# My_STM32_BOARD_SCH.net
KiCad netlist of a schematic drawn in Altium Designer
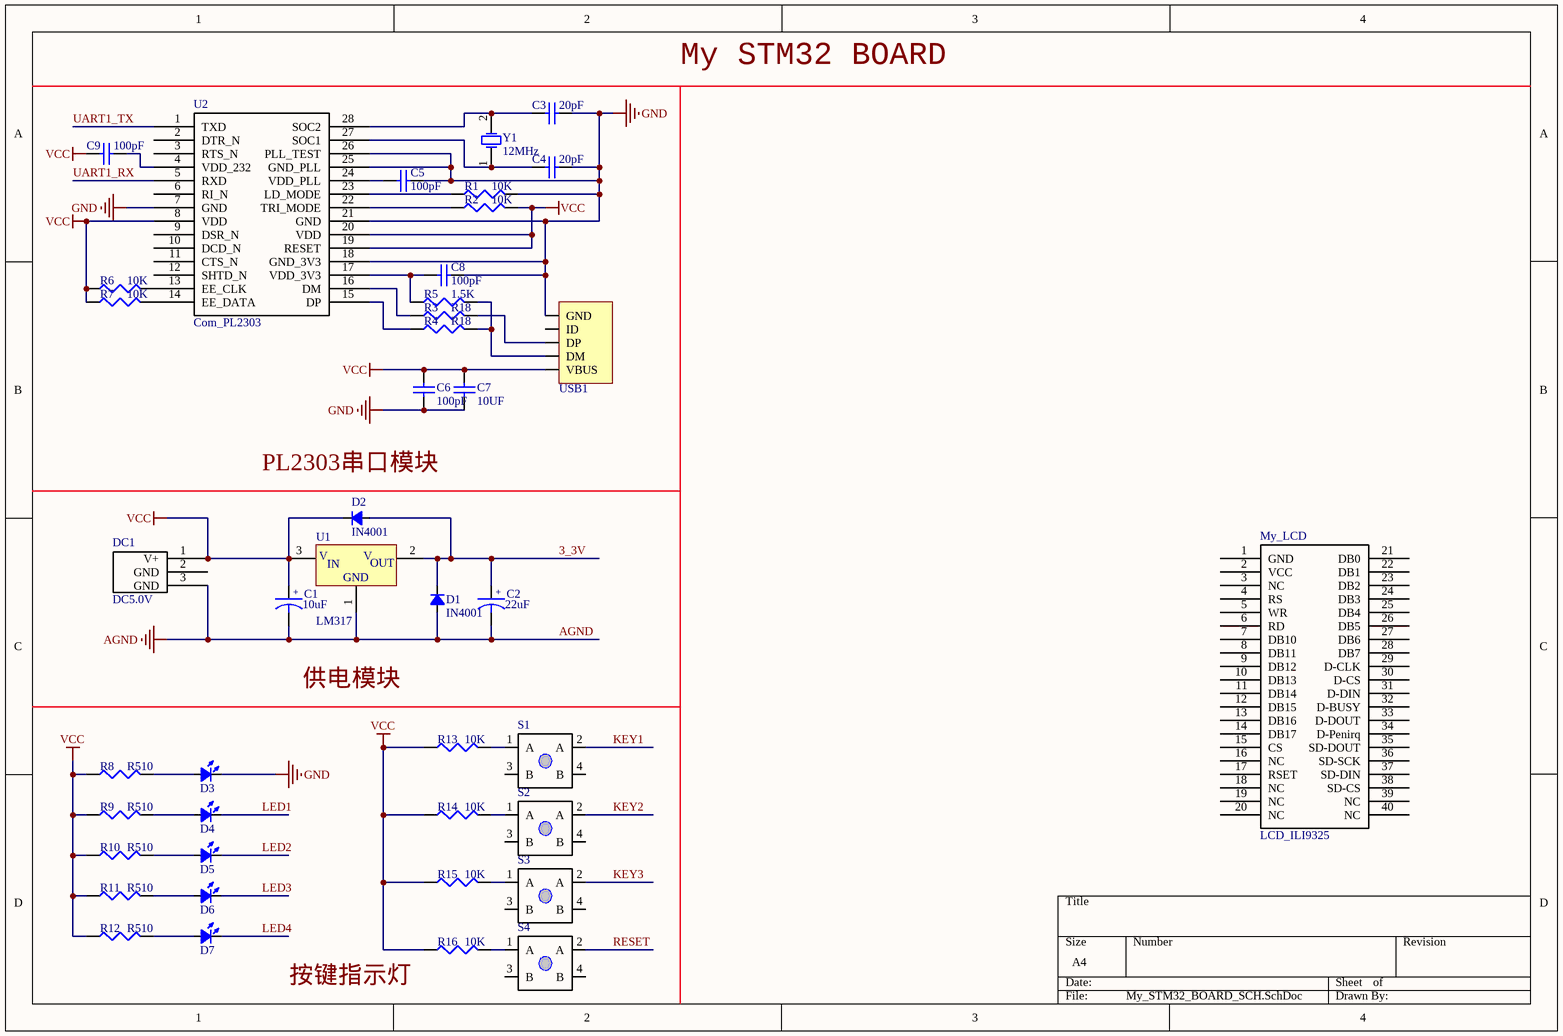
[diagram p0: My_STM32_BOARD_SCH.SchDoc]

(export (version "E")
  (design (tool "Eeschema 10.0.6"))
  (components
    (comp (ref "C1")
      (value "Cap_Pol")
      (footprint "Cap_Pol_F5")
      (description "Capacitor")
      (fields (field (name "ALTIUM_UNNAMED_1") "10uF"))
      (libsource (lib "My_Integrated_Library") (part "Cap_Pol"))
    )
    (comp (ref "C2")
      (value "22uF")
      (footprint "Cap_Pol_F6")
      (description "Capacitor")
      (fields (field (name "Comment") "Cap_Pol"))
      (libsource (lib "My_Integrated_Library") (part "Cap_Pol"))
    )
    (comp (ref "C3")
      (value "20pF")
      (footprint "0402")
      (description "Capacitor")
      (fields (field (name "Comment") "Cap") (field (name "PUBLISHER") "Altium Limited"))
      (libsource (lib "Miscellaneous Devices") (part "Cap"))
    )
    (comp (ref "C4")
      (value "20pF")
      (footprint "0402")
      (description "Capacitor")
      (fields (field (name "Comment") "Cap") (field (name "PUBLISHER") "Altium Limited"))
      (libsource (lib "Miscellaneous Devices") (part "Cap"))
    )
    (comp (ref "C5")
      (value "100pF")
      (footprint "0402")
      (description "Capacitor")
      (fields (field (name "Comment") "Cap") (field (name "PUBLISHER") "Altium Limited"))
      (libsource (lib "Miscellaneous Devices") (part "Cap"))
    )
    (comp (ref "C6")
      (value "100pF")
      (footprint "0402")
      (description "Capacitor")
      (fields (field (name "Comment") "Cap") (field (name "PUBLISHER") "Altium Limited"))
      (libsource (lib "Miscellaneous Devices") (part "Cap"))
    )
    (comp (ref "C7")
      (value "10UF")
      (footprint "2029")
      (description "Capacitor")
      (fields (field (name "Comment") "Cap") (field (name "PUBLISHER") "Altium Limited"))
      (libsource (lib "Miscellaneous Devices") (part "Cap"))
    )
    (comp (ref "C8")
      (value "100pF")
      (footprint "0402")
      (description "Capacitor")
      (fields (field (name "Comment") "Cap") (field (name "PUBLISHER") "Altium Limited"))
      (libsource (lib "Miscellaneous Devices") (part "Cap"))
    )
    (comp (ref "C9")
      (value "100pF")
      (footprint "0402")
      (description "Capacitor")
      (fields (field (name "Comment") "Cap") (field (name "PUBLISHER") "Altium Limited"))
      (libsource (lib "Miscellaneous Devices") (part "Cap"))
    )
    (comp (ref "D1")
      (value "IN4001")
      (footprint "DIODE_DO-214AC")
      (description "Diode")
      (libsource (lib "My_Integrated_Library") (part "Diode_SMA"))
    )
    (comp (ref "D2")
      (value "IN4001")
      (footprint "DIODE_DO-214AC")
      (description "Diode")
      (libsource (lib "My_Integrated_Library") (part "Diode_SMA"))
    )
    (comp (ref "D3")
      (value "LED_0805")
      (footprint "LED_0805_RED")
      (description "LED")
      (libsource (lib "My_Integrated_Library") (part "LED_0805"))
    )
    (comp (ref "D4")
      (value "LED_0805")
      (footprint "LED_1206_BLUE")
      (description "LED")
      (libsource (lib "My_Integrated_Library") (part "LED_0805"))
    )
    (comp (ref "D5")
      (value "LED_0805")
      (footprint "LED_1206_BLUE")
      (description "LED")
      (libsource (lib "My_Integrated_Library") (part "LED_0805"))
    )
    (comp (ref "D6")
      (value "LED_0805")
      (footprint "LED_1206_BLUE")
      (description "LED")
      (libsource (lib "My_Integrated_Library") (part "LED_0805"))
    )
    (comp (ref "D7")
      (value "LED_0805")
      (footprint "LED_1206_BLUE")
      (description "LED")
      (libsource (lib "My_Integrated_Library") (part "LED_0805"))
    )
    (comp (ref "DC1")
      (value "DC5.0V")
      (footprint "DC_5V")
      (libsource (lib "My_Integrated_Library") (part "DC5V"))
    )
    (comp (ref "My_LCD")
      (value "LCD_ILI9325")
      (footprint "ILI9325")
      (description "LCD ILI9325")
      (libsource (lib "My_Integrated_Library") (part "LCD_ILI9325"))
    )
    (comp (ref "R1")
      (value "10K")
      (footprint "6-0805_N")
      (description "Resistor")
      (fields (field (name "Comment") "Res3") (field (name "PUBLISHER") "Altium Limited"))
      (libsource (lib "Miscellaneous Devices") (part "Res3"))
    )
    (comp (ref "R2")
      (value "10K")
      (footprint "6-0805_N")
      (description "Resistor")
      (fields (field (name "Comment") "Res3") (field (name "PUBLISHER") "Altium Limited"))
      (libsource (lib "Miscellaneous Devices") (part "Res3"))
    )
    (comp (ref "R3")
      (value "R18")
      (footprint "6-0805_N")
      (description "Resistor")
      (fields (field (name "Comment") "Res3") (field (name "PUBLISHER") "Altium Limited"))
      (libsource (lib "Miscellaneous Devices") (part "Res3"))
    )
    (comp (ref "R4")
      (value "R18")
      (footprint "6-0805_N")
      (description "Resistor")
      (fields (field (name "Comment") "Res3") (field (name "PUBLISHER") "Altium Limited"))
      (libsource (lib "Miscellaneous Devices") (part "Res3"))
    )
    (comp (ref "R5")
      (value "1.5K")
      (footprint "6-0805_N")
      (description "Resistor")
      (fields (field (name "Comment") "Res3") (field (name "PUBLISHER") "Altium Limited"))
      (libsource (lib "Miscellaneous Devices") (part "Res3"))
    )
    (comp (ref "R6")
      (value "10K")
      (footprint "6-0805_N")
      (description "Resistor")
      (fields (field (name "Comment") "Res3") (field (name "PUBLISHER") "Altium Limited"))
      (libsource (lib "Miscellaneous Devices") (part "Res3"))
    )
    (comp (ref "R7")
      (value "10K")
      (footprint "6-0805_N")
      (description "Resistor")
      (fields (field (name "Comment") "Res3") (field (name "PUBLISHER") "Altium Limited"))
      (libsource (lib "Miscellaneous Devices") (part "Res3"))
    )
    (comp (ref "R8")
      (value "R510")
      (footprint "6-0805_N")
      (description "Resistor")
      (fields (field (name "Comment") "Res3") (field (name "PUBLISHER") "Altium Limited"))
      (libsource (lib "Miscellaneous Devices") (part "Res3"))
    )
    (comp (ref "R9")
      (value "R510")
      (footprint "6-0805_N")
      (description "Resistor")
      (fields (field (name "Comment") "Res3") (field (name "PUBLISHER") "Altium Limited"))
      (libsource (lib "Miscellaneous Devices") (part "Res3"))
    )
    (comp (ref "R10")
      (value "R510")
      (footprint "6-0805_N")
      (description "Resistor")
      (fields (field (name "Comment") "Res3") (field (name "PUBLISHER") "Altium Limited"))
      (libsource (lib "Miscellaneous Devices") (part "Res3"))
    )
    (comp (ref "R11")
      (value "R510")
      (footprint "6-0805_N")
      (description "Resistor")
      (fields (field (name "Comment") "Res3") (field (name "PUBLISHER") "Altium Limited"))
      (libsource (lib "Miscellaneous Devices") (part "Res3"))
    )
    (comp (ref "R12")
      (value "R510")
      (footprint "6-0805_N")
      (description "Resistor")
      (fields (field (name "Comment") "Res3") (field (name "PUBLISHER") "Altium Limited"))
      (libsource (lib "Miscellaneous Devices") (part "Res3"))
    )
    (comp (ref "R13")
      (value "10K")
      (footprint "6-0805_N")
      (description "Resistor")
      (fields (field (name "Comment") "Res3") (field (name "PUBLISHER") "Altium Limited"))
      (libsource (lib "Miscellaneous Devices") (part "Res3"))
    )
    (comp (ref "R14")
      (value "10K")
      (footprint "6-0805_N")
      (description "Resistor")
      (fields (field (name "Comment") "Res3") (field (name "PUBLISHER") "Altium Limited"))
      (libsource (lib "Miscellaneous Devices") (part "Res3"))
    )
    (comp (ref "R15")
      (value "10K")
      (footprint "6-0805_N")
      (description "Resistor")
      (fields (field (name "Comment") "Res3") (field (name "PUBLISHER") "Altium Limited"))
      (libsource (lib "Miscellaneous Devices") (part "Res3"))
    )
    (comp (ref "R16")
      (value "10K")
      (footprint "6-0805_N")
      (description "Resistor")
      (fields (field (name "Comment") "Res3") (field (name "PUBLISHER") "Altium Limited"))
      (libsource (lib "Miscellaneous Devices") (part "Res3"))
    )
    (comp (ref "S1")
      (value "Button")
      (footprint "My_Button")
      (description "四脚按键")
      (libsource (lib "My_Integrated_Library") (part "KEY_K4"))
    )
    (comp (ref "S2")
      (value "Button")
      (footprint "My_Button")
      (description "四脚按键")
      (libsource (lib "My_Integrated_Library") (part "KEY_K4"))
    )
    (comp (ref "S3")
      (value "Button")
      (footprint "My_Button")
      (description "四脚按键")
      (libsource (lib "My_Integrated_Library") (part "KEY_K4"))
    )
    (comp (ref "S4")
      (value "Button")
      (footprint "My_Button")
      (description "四脚按键")
      (libsource (lib "My_Integrated_Library") (part "KEY_K4"))
    )
    (comp (ref "U1")
      (value "LM317")
      (footprint "lm1117")
      (description "LM317 电源芯片")
      (libsource (lib "My_Integrated_Library") (part "Power_LM317"))
    )
    (comp (ref "U2")
      (value "Com_PL2303")
      (footprint "SSOP-28")
      (description "PL2303")
      (libsource (lib "My_Integrated_Library") (part "Com_PL2303"))
    )
    (comp (ref "USB1")
      (value "USB_Mini")
      (footprint "USB_MINI-B")
      (description "USB")
      (libsource (lib "My_Integrated_Library") (part "USB_Mini"))
    )
    (comp (ref "Y1")
      (value "12MHz")
      (footprint "XT_XTAL")
      (description "XTAL")
      (libsource (lib "My_Integrated_Library") (part "XTAL"))
    )
  )
  (nets
    (net (code "1") (name "/3_3V") (class "Default")
      (node (ref "C2") (pin "1") (pinfunction "1_1") (pintype "passive"))
      (node (ref "D1") (pin "2") (pinfunction "K_2") (pintype "passive"))
      (node (ref "D2") (pin "1") (pinfunction "A_1") (pintype "passive"))
      (node (ref "U1") (pin "2") (pinfunction "VOUT_2") (pintype "passive"))
    )
    (net (code "2") (name "/KEY1") (class "Default")
      (node (ref "S1") (pin "2") (pinfunction "A_2") (pintype "passive"))
    )
    (net (code "3") (name "/KEY2") (class "Default")
      (node (ref "S2") (pin "2") (pinfunction "A_2") (pintype "passive"))
    )
    (net (code "4") (name "/KEY3") (class "Default")
      (node (ref "S3") (pin "2") (pinfunction "A_2") (pintype "passive"))
    )
    (net (code "5") (name "/LED1") (class "Default")
      (node (ref "D4") (pin "2") (pinfunction "K_2") (pintype "passive"))
    )
    (net (code "6") (name "/LED2") (class "Default")
      (node (ref "D5") (pin "2") (pinfunction "K_2") (pintype "passive"))
    )
    (net (code "7") (name "/LED3") (class "Default")
      (node (ref "D6") (pin "2") (pinfunction "K_2") (pintype "passive"))
    )
    (net (code "8") (name "/LED4") (class "Default")
      (node (ref "D7") (pin "2") (pinfunction "K_2") (pintype "passive"))
    )
    (net (code "9") (name "/RESET") (class "Default")
      (node (ref "S4") (pin "2") (pinfunction "A_2") (pintype "passive"))
    )
    (net (code "10") (name "/UART1_RX") (class "Default")
      (node (ref "U2") (pin "5") (pinfunction "RXD_5") (pintype "passive"))
    )
    (net (code "11") (name "/UART1_TX") (class "Default")
      (node (ref "U2") (pin "1") (pinfunction "TXD_1") (pintype "passive"))
    )
    (net (code "12") (name "AGND") (class "Default")
      (node (ref "C1") (pin "2") (pinfunction "2_2") (pintype "passive"))
      (node (ref "C2") (pin "2") (pinfunction "2_2") (pintype "passive"))
      (node (ref "D1") (pin "1") (pinfunction "A_1") (pintype "passive"))
      (node (ref "DC1") (pin "3") (pinfunction "GND_3") (pintype "passive"))
      (node (ref "U1") (pin "1") (pinfunction "GND_1") (pintype "passive"))
    )
    (net (code "13") (name "GND") (class "Default")
      (node (ref "C3") (pin "2") (pinfunction "2_2") (pintype "passive"))
      (node (ref "C4") (pin "2") (pinfunction "2_2") (pintype "passive"))
      (node (ref "C5") (pin "2") (pinfunction "2_2") (pintype "passive"))
      (node (ref "C6") (pin "1") (pinfunction "1_1") (pintype "passive"))
      (node (ref "C7") (pin "1") (pinfunction "1_1") (pintype "passive"))
      (node (ref "C8") (pin "2") (pinfunction "2_2") (pintype "passive"))
      (node (ref "D3") (pin "2") (pinfunction "K_2") (pintype "passive"))
      (node (ref "R1") (pin "2") (pinfunction "2_2") (pintype "passive"))
      (node (ref "U2") (pin "18") (pinfunction "GND_3V3_18") (pintype "passive"))
      (node (ref "U2") (pin "21") (pinfunction "GND_21") (pintype "passive"))
      (node (ref "U2") (pin "25") (pinfunction "GND_PLL_25") (pintype "passive"))
      (node (ref "U2") (pin "26") (pinfunction "PLL_TEST_26") (pintype "passive"))
      (node (ref "U2") (pin "7") (pinfunction "GND_7") (pintype "passive"))
      (node (ref "USB1") (pin "5") (pinfunction "GND_5") (pintype "passive"))
    )
    (net (code "14") (name "Net-(D3-A)") (class "Default")
      (node (ref "D3") (pin "1") (pinfunction "A_1") (pintype "passive"))
      (node (ref "R8") (pin "2") (pinfunction "2_2") (pintype "passive"))
    )
    (net (code "15") (name "Net-(D4-A)") (class "Default")
      (node (ref "D4") (pin "1") (pinfunction "A_1") (pintype "passive"))
      (node (ref "R9") (pin "2") (pinfunction "2_2") (pintype "passive"))
    )
    (net (code "16") (name "Net-(D5-A)") (class "Default")
      (node (ref "D5") (pin "1") (pinfunction "A_1") (pintype "passive"))
      (node (ref "R10") (pin "2") (pinfunction "2_2") (pintype "passive"))
    )
    (net (code "17") (name "Net-(D6-A)") (class "Default")
      (node (ref "D6") (pin "1") (pinfunction "A_1") (pintype "passive"))
      (node (ref "R11") (pin "2") (pinfunction "2_2") (pintype "passive"))
    )
    (net (code "18") (name "Net-(D7-A)") (class "Default")
      (node (ref "D7") (pin "1") (pinfunction "A_1") (pintype "passive"))
      (node (ref "R12") (pin "2") (pinfunction "2_2") (pintype "passive"))
    )
    (net (code "19") (name "Net-(R13-Pad2)") (class "Default")
      (node (ref "R13") (pin "2") (pinfunction "2_2") (pintype "passive"))
      (node (ref "S1") (pin "1") (pinfunction "A_1") (pintype "passive"))
    )
    (net (code "20") (name "Net-(R14-Pad2)") (class "Default")
      (node (ref "R14") (pin "2") (pinfunction "2_2") (pintype "passive"))
      (node (ref "S2") (pin "1") (pinfunction "A_1") (pintype "passive"))
    )
    (net (code "21") (name "Net-(R15-Pad2)") (class "Default")
      (node (ref "R15") (pin "2") (pinfunction "2_2") (pintype "passive"))
      (node (ref "S3") (pin "1") (pinfunction "A_1") (pintype "passive"))
    )
    (net (code "22") (name "Net-(R16-Pad2)") (class "Default")
      (node (ref "R16") (pin "2") (pinfunction "2_2") (pintype "passive"))
      (node (ref "S4") (pin "1") (pinfunction "A_1") (pintype "passive"))
    )
    (net (code "23") (name "Net-(U2-DM)") (class "Default")
      (node (ref "R3") (pin "1") (pinfunction "1_1") (pintype "passive"))
      (node (ref "U2") (pin "16") (pinfunction "DM_16") (pintype "passive"))
    )
    (net (code "24") (name "Net-(U2-DP)") (class "Default")
      (node (ref "R4") (pin "1") (pinfunction "1_1") (pintype "passive"))
      (node (ref "U2") (pin "15") (pinfunction "DP_15") (pintype "passive"))
    )
    (net (code "25") (name "Net-(U2-EE_CLK)") (class "Default")
      (node (ref "R6") (pin "2") (pinfunction "2_2") (pintype "passive"))
      (node (ref "U2") (pin "13") (pinfunction "EE_CLK_13") (pintype "passive"))
    )
    (net (code "26") (name "Net-(U2-EE_DATA)") (class "Default")
      (node (ref "R7") (pin "2") (pinfunction "2_2") (pintype "passive"))
      (node (ref "U2") (pin "14") (pinfunction "EE_DATA_14") (pintype "passive"))
    )
    (net (code "27") (name "Net-(U2-LD_MODE)") (class "Default")
      (node (ref "R1") (pin "1") (pinfunction "1_1") (pintype "passive"))
      (node (ref "U2") (pin "23") (pinfunction "LD_MODE_23") (pintype "passive"))
    )
    (net (code "28") (name "Net-(U2-SOC1)") (class "Default")
      (node (ref "C4") (pin "1") (pinfunction "1_1") (pintype "passive"))
      (node (ref "U2") (pin "27") (pinfunction "SOC1_27") (pintype "passive"))
      (node (ref "Y1") (pin "1") (pinfunction "1_1") (pintype "passive"))
    )
    (net (code "29") (name "Net-(U2-SOC2)") (class "Default")
      (node (ref "C3") (pin "1") (pinfunction "1_1") (pintype "passive"))
      (node (ref "U2") (pin "28") (pinfunction "SOC2_28") (pintype "passive"))
      (node (ref "Y1") (pin "2") (pinfunction "2_2") (pintype "passive"))
    )
    (net (code "30") (name "Net-(U2-TRI_MODE)") (class "Default")
      (node (ref "R2") (pin "1") (pinfunction "1_1") (pintype "passive"))
      (node (ref "U2") (pin "22") (pinfunction "TRI_MODE_22") (pintype "passive"))
    )
    (net (code "31") (name "Net-(U2-VDD_3V3)") (class "Default")
      (node (ref "C8") (pin "1") (pinfunction "1_1") (pintype "passive"))
      (node (ref "R5") (pin "1") (pinfunction "1_1") (pintype "passive"))
      (node (ref "U2") (pin "17") (pinfunction "VDD_3V3_17") (pintype "passive"))
    )
    (net (code "32") (name "Net-(U2-VDD_232)") (class "Default")
      (node (ref "C9") (pin "1") (pinfunction "1_1") (pintype "passive"))
      (node (ref "U2") (pin "4") (pinfunction "VDD_232_4") (pintype "passive"))
    )
    (net (code "33") (name "Net-(U2-VDD_PLL)") (class "Default")
      (node (ref "C5") (pin "1") (pinfunction "1_1") (pintype "passive"))
      (node (ref "U2") (pin "24") (pinfunction "VDD_PLL_24") (pintype "passive"))
    )
    (net (code "34") (name "Net-(USB1-DM)") (class "Default")
      (node (ref "R4") (pin "2") (pinfunction "2_2") (pintype "passive"))
      (node (ref "R5") (pin "2") (pinfunction "2_2") (pintype "passive"))
      (node (ref "USB1") (pin "2") (pinfunction "DM_2") (pintype "passive"))
    )
    (net (code "35") (name "Net-(USB1-DP)") (class "Default")
      (node (ref "R3") (pin "2") (pinfunction "2_2") (pintype "passive"))
      (node (ref "USB1") (pin "3") (pinfunction "DP_3") (pintype "passive"))
    )
    (net (code "36") (name "VCC") (class "Default")
      (node (ref "C1") (pin "1") (pinfunction "1_1") (pintype "passive"))
      (node (ref "C6") (pin "2") (pinfunction "2_2") (pintype "passive"))
      (node (ref "C7") (pin "2") (pinfunction "2_2") (pintype "passive"))
      (node (ref "C9") (pin "2") (pinfunction "2_2") (pintype "passive"))
      (node (ref "D2") (pin "2") (pinfunction "K_2") (pintype "passive"))
      (node (ref "DC1") (pin "1") (pinfunction "V+_1") (pintype "passive"))
      (node (ref "R10") (pin "1") (pinfunction "1_1") (pintype "passive"))
      (node (ref "R11") (pin "1") (pinfunction "1_1") (pintype "passive"))
      (node (ref "R12") (pin "1") (pinfunction "1_1") (pintype "passive"))
      (node (ref "R13") (pin "1") (pinfunction "1_1") (pintype "passive"))
      (node (ref "R14") (pin "1") (pinfunction "1_1") (pintype "passive"))
      (node (ref "R15") (pin "1") (pinfunction "1_1") (pintype "passive"))
      (node (ref "R16") (pin "1") (pinfunction "1_1") (pintype "passive"))
      (node (ref "R2") (pin "2") (pinfunction "2_2") (pintype "passive"))
      (node (ref "R6") (pin "1") (pinfunction "1_1") (pintype "passive"))
      (node (ref "R7") (pin "1") (pinfunction "1_1") (pintype "passive"))
      (node (ref "R8") (pin "1") (pinfunction "1_1") (pintype "passive"))
      (node (ref "R9") (pin "1") (pinfunction "1_1") (pintype "passive"))
      (node (ref "U1") (pin "3") (pinfunction "VIN_3") (pintype "passive"))
      (node (ref "U2") (pin "19") (pinfunction "RESET_19") (pintype "passive"))
      (node (ref "U2") (pin "20") (pinfunction "VDD_20") (pintype "passive"))
      (node (ref "U2") (pin "8") (pinfunction "VDD_8") (pintype "passive"))
      (node (ref "USB1") (pin "1") (pinfunction "VBUS_1") (pintype "passive"))
    )
    (net (code "37") (name "unconnected-(DC1-GND-Pad2)") (class "Default")
      (node (ref "DC1") (pin "2") (pinfunction "GND_2") (pintype "passive"))
    )
    (net (code "38") (name "unconnected-(My_LCD-CS-Pad15)") (class "Default")
      (node (ref "My_LCD") (pin "15") (pinfunction "CS_15") (pintype "passive"))
    )
    (net (code "39") (name "unconnected-(My_LCD-D-BUSY-Pad32)") (class "Default")
      (node (ref "My_LCD") (pin "32") (pinfunction "D-BUSY_32") (pintype "passive"))
    )
    (net (code "40") (name "unconnected-(My_LCD-D-CLK-Pad29)") (class "Default")
      (node (ref "My_LCD") (pin "29") (pinfunction "D-CLK_29") (pintype "passive"))
    )
    (net (code "41") (name "unconnected-(My_LCD-D-CS-Pad30)") (class "Default")
      (node (ref "My_LCD") (pin "30") (pinfunction "D-CS_30") (pintype "passive"))
    )
    (net (code "42") (name "unconnected-(My_LCD-D-DIN-Pad31)") (class "Default")
      (node (ref "My_LCD") (pin "31") (pinfunction "D-DIN_31") (pintype "passive"))
    )
    (net (code "43") (name "unconnected-(My_LCD-D-DOUT-Pad33)") (class "Default")
      (node (ref "My_LCD") (pin "33") (pinfunction "D-DOUT_33") (pintype "passive"))
    )
    (net (code "44") (name "unconnected-(My_LCD-D-Penirq-Pad34)") (class "Default")
      (node (ref "My_LCD") (pin "34") (pinfunction "D-Penirq_34") (pintype "passive"))
    )
    (net (code "45") (name "unconnected-(My_LCD-DB0-Pad21)") (class "Default")
      (node (ref "My_LCD") (pin "21") (pinfunction "DB0_21") (pintype "passive"))
    )
    (net (code "46") (name "unconnected-(My_LCD-DB1-Pad22)") (class "Default")
      (node (ref "My_LCD") (pin "22") (pinfunction "DB1_22") (pintype "passive"))
    )
    (net (code "47") (name "unconnected-(My_LCD-DB2-Pad23)") (class "Default")
      (node (ref "My_LCD") (pin "23") (pinfunction "DB2_23") (pintype "passive"))
    )
    (net (code "48") (name "unconnected-(My_LCD-DB3-Pad24)") (class "Default")
      (node (ref "My_LCD") (pin "24") (pinfunction "DB3_24") (pintype "passive"))
    )
    (net (code "49") (name "unconnected-(My_LCD-DB4-Pad25)") (class "Default")
      (node (ref "My_LCD") (pin "25") (pinfunction "DB4_25") (pintype "passive"))
    )
    (net (code "50") (name "unconnected-(My_LCD-DB5-Pad26)") (class "Default")
      (node (ref "My_LCD") (pin "26") (pinfunction "DB5_26") (pintype "passive"))
    )
    (net (code "51") (name "unconnected-(My_LCD-DB6-Pad27)") (class "Default")
      (node (ref "My_LCD") (pin "27") (pinfunction "DB6_27") (pintype "passive"))
    )
    (net (code "52") (name "unconnected-(My_LCD-DB7-Pad28)") (class "Default")
      (node (ref "My_LCD") (pin "28") (pinfunction "DB7_28") (pintype "passive"))
    )
    (net (code "53") (name "unconnected-(My_LCD-DB10-Pad7)") (class "Default")
      (node (ref "My_LCD") (pin "7") (pinfunction "DB10_7") (pintype "passive"))
    )
    (net (code "54") (name "unconnected-(My_LCD-DB11-Pad8)") (class "Default")
      (node (ref "My_LCD") (pin "8") (pinfunction "DB11_8") (pintype "passive"))
    )
    (net (code "55") (name "unconnected-(My_LCD-DB12-Pad9)") (class "Default")
      (node (ref "My_LCD") (pin "9") (pinfunction "DB12_9") (pintype "passive"))
    )
    (net (code "56") (name "unconnected-(My_LCD-DB13-Pad10)") (class "Default")
      (node (ref "My_LCD") (pin "10") (pinfunction "DB13_10") (pintype "passive"))
    )
    (net (code "57") (name "unconnected-(My_LCD-DB14-Pad11)") (class "Default")
      (node (ref "My_LCD") (pin "11") (pinfunction "DB14_11") (pintype "passive"))
    )
    (net (code "58") (name "unconnected-(My_LCD-DB15-Pad12)") (class "Default")
      (node (ref "My_LCD") (pin "12") (pinfunction "DB15_12") (pintype "passive"))
    )
    (net (code "59") (name "unconnected-(My_LCD-DB16-Pad13)") (class "Default")
      (node (ref "My_LCD") (pin "13") (pinfunction "DB16_13") (pintype "passive"))
    )
    (net (code "60") (name "unconnected-(My_LCD-DB17-Pad14)") (class "Default")
      (node (ref "My_LCD") (pin "14") (pinfunction "DB17_14") (pintype "passive"))
    )
    (net (code "61") (name "unconnected-(My_LCD-GND-Pad1)") (class "Default")
      (node (ref "My_LCD") (pin "1") (pinfunction "GND_1") (pintype "passive"))
    )
    (net (code "62") (name "unconnected-(My_LCD-NC-Pad3)") (class "Default")
      (node (ref "My_LCD") (pin "3") (pinfunction "NC_3") (pintype "passive"))
    )
    (net (code "63") (name "unconnected-(My_LCD-NC-Pad16)") (class "Default")
      (node (ref "My_LCD") (pin "16") (pinfunction "NC_16") (pintype "passive"))
    )
    (net (code "64") (name "unconnected-(My_LCD-NC-Pad18)") (class "Default")
      (node (ref "My_LCD") (pin "18") (pinfunction "NC_18") (pintype "passive"))
    )
    (net (code "65") (name "unconnected-(My_LCD-NC-Pad19)") (class "Default")
      (node (ref "My_LCD") (pin "19") (pinfunction "NC_19") (pintype "passive"))
    )
    (net (code "66") (name "unconnected-(My_LCD-NC-Pad20)") (class "Default")
      (node (ref "My_LCD") (pin "20") (pinfunction "NC_20") (pintype "passive"))
    )
    (net (code "67") (name "unconnected-(My_LCD-NC-Pad39)") (class "Default")
      (node (ref "My_LCD") (pin "39") (pinfunction "NC_39") (pintype "passive"))
    )
    (net (code "68") (name "unconnected-(My_LCD-NC-Pad40)") (class "Default")
      (node (ref "My_LCD") (pin "40") (pinfunction "NC_40") (pintype "passive"))
    )
    (net (code "69") (name "unconnected-(My_LCD-RD-Pad6)") (class "Default")
      (node (ref "My_LCD") (pin "6") (pinfunction "RD_6") (pintype "passive"))
    )
    (net (code "70") (name "unconnected-(My_LCD-RS-Pad4)") (class "Default")
      (node (ref "My_LCD") (pin "4") (pinfunction "RS_4") (pintype "passive"))
    )
    (net (code "71") (name "unconnected-(My_LCD-RSET-Pad17)") (class "Default")
      (node (ref "My_LCD") (pin "17") (pinfunction "RSET_17") (pintype "passive"))
    )
    (net (code "72") (name "unconnected-(My_LCD-SD-CS-Pad38)") (class "Default")
      (node (ref "My_LCD") (pin "38") (pinfunction "SD-CS_38") (pintype "passive"))
    )
    (net (code "73") (name "unconnected-(My_LCD-SD-DIN-Pad37)") (class "Default")
      (node (ref "My_LCD") (pin "37") (pinfunction "SD-DIN_37") (pintype "passive"))
    )
    (net (code "74") (name "unconnected-(My_LCD-SD-DOUT-Pad35)") (class "Default")
      (node (ref "My_LCD") (pin "35") (pinfunction "SD-DOUT_35") (pintype "passive"))
    )
    (net (code "75") (name "unconnected-(My_LCD-SD-SCK-Pad36)") (class "Default")
      (node (ref "My_LCD") (pin "36") (pinfunction "SD-SCK_36") (pintype "passive"))
    )
    (net (code "76") (name "unconnected-(My_LCD-VCC-Pad2)") (class "Default")
      (node (ref "My_LCD") (pin "2") (pinfunction "VCC_2") (pintype "passive"))
    )
    (net (code "77") (name "unconnected-(My_LCD-WR-Pad5)") (class "Default")
      (node (ref "My_LCD") (pin "5") (pinfunction "WR_5") (pintype "passive"))
    )
    (net (code "78") (name "unconnected-(S1-B-Pad3)") (class "Default")
      (node (ref "S1") (pin "3") (pinfunction "B_3") (pintype "passive"))
    )
    (net (code "79") (name "unconnected-(S1-B-Pad4)") (class "Default")
      (node (ref "S1") (pin "4") (pinfunction "B_4") (pintype "passive"))
    )
    (net (code "80") (name "unconnected-(S2-B-Pad3)") (class "Default")
      (node (ref "S2") (pin "3") (pinfunction "B_3") (pintype "passive"))
    )
    (net (code "81") (name "unconnected-(S2-B-Pad4)") (class "Default")
      (node (ref "S2") (pin "4") (pinfunction "B_4") (pintype "passive"))
    )
    (net (code "82") (name "unconnected-(S3-B-Pad3)") (class "Default")
      (node (ref "S3") (pin "3") (pinfunction "B_3") (pintype "passive"))
    )
    (net (code "83") (name "unconnected-(S3-B-Pad4)") (class "Default")
      (node (ref "S3") (pin "4") (pinfunction "B_4") (pintype "passive"))
    )
    (net (code "84") (name "unconnected-(S4-B-Pad3)") (class "Default")
      (node (ref "S4") (pin "3") (pinfunction "B_3") (pintype "passive"))
    )
    (net (code "85") (name "unconnected-(S4-B-Pad4)") (class "Default")
      (node (ref "S4") (pin "4") (pinfunction "B_4") (pintype "passive"))
    )
    (net (code "86") (name "unconnected-(U2-CTS_N-Pad11)") (class "Default")
      (node (ref "U2") (pin "11") (pinfunction "CTS_N_11") (pintype "passive"))
    )
    (net (code "87") (name "unconnected-(U2-DCD_N-Pad10)") (class "Default")
      (node (ref "U2") (pin "10") (pinfunction "DCD_N_10") (pintype "passive"))
    )
    (net (code "88") (name "unconnected-(U2-DSR_N-Pad9)") (class "Default")
      (node (ref "U2") (pin "9") (pinfunction "DSR_N_9") (pintype "passive"))
    )
    (net (code "89") (name "unconnected-(U2-DTR_N-Pad2)") (class "Default")
      (node (ref "U2") (pin "2") (pinfunction "DTR_N_2") (pintype "passive"))
    )
    (net (code "90") (name "unconnected-(U2-RI_N-Pad6)") (class "Default")
      (node (ref "U2") (pin "6") (pinfunction "RI_N_6") (pintype "passive"))
    )
    (net (code "91") (name "unconnected-(U2-RTS_N-Pad3)") (class "Default")
      (node (ref "U2") (pin "3") (pinfunction "RTS_N_3") (pintype "passive"))
    )
    (net (code "92") (name "unconnected-(U2-SHTD_N-Pad12)") (class "Default")
      (node (ref "U2") (pin "12") (pinfunction "SHTD_N_12") (pintype "passive"))
    )
    (net (code "93") (name "unconnected-(USB1-ID-Pad4)") (class "Default")
      (node (ref "USB1") (pin "4") (pinfunction "ID_4") (pintype "passive"))
    )
  )
)
